# Connectors.net
KiCad netlist of a schematic drawn in Altium Designer
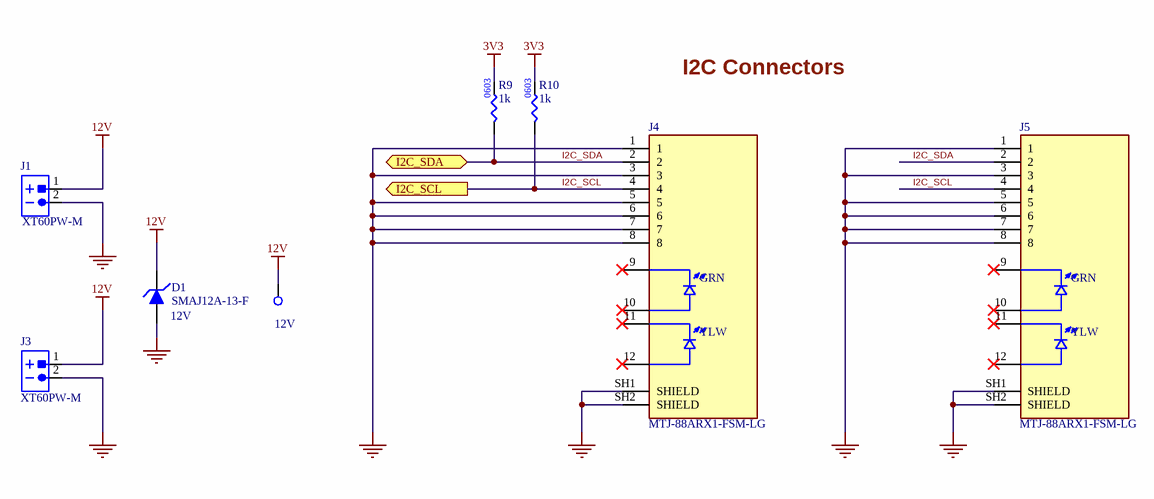
[diagram p0: Connectors.SchDoc]

(export (version "E")
  (design (tool "Eeschema 10.0.6"))
  (components
    (comp (ref "12V")
      (value "RCWCTE")
      (footprint "RCWCTE")
      (description "SMT Test Point")
      (fields (field (name "MANUFACTURER") "KOA Speer"))
      (libsource (lib "PuttPilot") (part "RCWCTE"))
    )
    (comp (ref "D1")
      (value "SMAJ12A-13-F")
      (footprint "SMAJ12A-13-F")
      (description "TVS DIODE 12VWM")
      (fields (field (name "MANUFACTURER") "Diodes") (field (name "REP PK REVERSE VOLTAGE-MAX") "12V"))
      (libsource (lib "PuttPilot") (part "SMAJ12A-13-F"))
    )
    (comp (ref "J1")
      (value "XT60PW-M")
      (footprint "XT60PW-M")
      (description "XT60PW Male")
      (fields (field (name "MANUFACTURER") "Unclassified"))
      (libsource (lib "PuttPilot") (part "XT60PW-M"))
    )
    (comp (ref "J3")
      (value "XT60PW-M")
      (footprint "XT60PW-M")
      (description "XT60PW Male")
      (fields (field (name "MANUFACTURER") "Unclassified"))
      (libsource (lib "PuttPilot") (part "XT60PW-M"))
    )
    (comp (ref "J4")
      (value "MTJ-88ARX1-FSM-LG")
      (footprint "MTJ-88ARX1-FSM-LG")
      (description "RJ45 JACK R/A SHIELDED")
      (fields (field (name "MANUFACTURER") "Adam Equipment"))
      (libsource (lib "PuttPilot") (part "MTJ-88ARX1-FSM-LG"))
    )
    (comp (ref "J5")
      (value "MTJ-88ARX1-FSM-LG")
      (footprint "MTJ-88ARX1-FSM-LG")
      (description "RJ45 JACK R/A SHIELDED")
      (fields (field (name "MANUFACTURER") "Adam Equipment"))
      (libsource (lib "PuttPilot") (part "MTJ-88ARX1-FSM-LG"))
    )
    (comp (ref "R9")
      (value "RC0603FR-071KL")
      (footprint ".RES_0603")
      (description "RES 1K OHM 0603")
      (fields
        (field (name "MANUFACTURER") "Yageo")
        (field (name "TOLERANCE") "1%")
        (field (name "RESISTANCE") "1k")
      )
      (libsource (lib "PuttPilot") (part "RC0603FR-071KL"))
    )
    (comp (ref "R10")
      (value "RC0603FR-071KL")
      (footprint ".RES_0603")
      (description "RES 1K OHM 0603")
      (fields
        (field (name "MANUFACTURER") "Yageo")
        (field (name "TOLERANCE") "1%")
        (field (name "RESISTANCE") "1k")
      )
      (libsource (lib "PuttPilot") (part "RC0603FR-071KL"))
    )
  )
  (nets
    (net (code "1") (name "/I2C_SCL") (class "Default")
      (node (ref "J4") (pin "4") (pinfunction "4_4") (pintype "passive"))
      (node (ref "J5") (pin "4") (pinfunction "4_4") (pintype "passive"))
      (node (ref "R10") (pin "1") (pinfunction "1_1") (pintype "passive"))
    )
    (net (code "2") (name "/I2C_SDA") (class "Default")
      (node (ref "J4") (pin "2") (pinfunction "2_2") (pintype "passive"))
      (node (ref "J5") (pin "2") (pinfunction "2_2") (pintype "passive"))
      (node (ref "R9") (pin "1") (pinfunction "1_1") (pintype "passive"))
    )
    (net (code "3") (name "3V3") (class "Default")
      (node (ref "R10") (pin "2") (pinfunction "2_2") (pintype "passive"))
      (node (ref "R9") (pin "2") (pinfunction "2_2") (pintype "passive"))
    )
    (net (code "4") (name "12V") (class "Default")
      (node (ref "12V") (pin "1") (pinfunction "1_1") (pintype "passive"))
      (node (ref "D1") (pin "2") (pinfunction "Pin_2_2") (pintype "passive"))
      (node (ref "J1") (pin "1") (pinfunction "1_1") (pintype "passive"))
      (node (ref "J3") (pin "1") (pinfunction "1_1") (pintype "passive"))
    )
    (net (code "5") (name "GND") (class "Default")
      (node (ref "D1") (pin "1") (pinfunction "Pin_1_1") (pintype "passive"))
      (node (ref "J1") (pin "2") (pinfunction "2_2") (pintype "passive"))
      (node (ref "J3") (pin "2") (pinfunction "2_2") (pintype "passive"))
      (node (ref "J4") (pin "1") (pinfunction "1_1") (pintype "passive"))
      (node (ref "J4") (pin "3") (pinfunction "3_3") (pintype "passive"))
      (node (ref "J4") (pin "5") (pinfunction "5_5") (pintype "passive"))
      (node (ref "J4") (pin "6") (pinfunction "6_6") (pintype "passive"))
      (node (ref "J4") (pin "7") (pinfunction "7_7") (pintype "passive"))
      (node (ref "J4") (pin "8") (pinfunction "8_8") (pintype "passive"))
      (node (ref "J4") (pin "SH1") (pinfunction "SHIELD_SH1") (pintype "passive"))
      (node (ref "J4") (pin "SH2") (pinfunction "SHIELD_SH2") (pintype "passive"))
      (node (ref "J5") (pin "1") (pinfunction "1_1") (pintype "passive"))
      (node (ref "J5") (pin "3") (pinfunction "3_3") (pintype "passive"))
      (node (ref "J5") (pin "5") (pinfunction "5_5") (pintype "passive"))
      (node (ref "J5") (pin "6") (pinfunction "6_6") (pintype "passive"))
      (node (ref "J5") (pin "7") (pinfunction "7_7") (pintype "passive"))
      (node (ref "J5") (pin "8") (pinfunction "8_8") (pintype "passive"))
      (node (ref "J5") (pin "SH1") (pinfunction "SHIELD_SH1") (pintype "passive"))
      (node (ref "J5") (pin "SH2") (pinfunction "SHIELD_SH2") (pintype "passive"))
    )
    (net (code "6") (name "unconnected-(J4-Pad9)") (class "Default")
      (node (ref "J4") (pin "9") (pinfunction "9_9") (pintype "passive+no_connect"))
    )
    (net (code "7") (name "unconnected-(J4-Pad10)") (class "Default")
      (node (ref "J4") (pin "10") (pinfunction "10_10") (pintype "passive+no_connect"))
    )
    (net (code "8") (name "unconnected-(J4-Pad11)") (class "Default")
      (node (ref "J4") (pin "11") (pinfunction "11_11") (pintype "passive+no_connect"))
    )
    (net (code "9") (name "unconnected-(J4-Pad12)") (class "Default")
      (node (ref "J4") (pin "12") (pinfunction "12_12") (pintype "passive+no_connect"))
    )
    (net (code "10") (name "unconnected-(J5-Pad9)") (class "Default")
      (node (ref "J5") (pin "9") (pinfunction "9_9") (pintype "passive+no_connect"))
    )
    (net (code "11") (name "unconnected-(J5-Pad10)") (class "Default")
      (node (ref "J5") (pin "10") (pinfunction "10_10") (pintype "passive+no_connect"))
    )
    (net (code "12") (name "unconnected-(J5-Pad11)") (class "Default")
      (node (ref "J5") (pin "11") (pinfunction "11_11") (pintype "passive+no_connect"))
    )
    (net (code "13") (name "unconnected-(J5-Pad12)") (class "Default")
      (node (ref "J5") (pin "12") (pinfunction "12_12") (pintype "passive+no_connect"))
    )
  )
)
